# XIAO-MIC.net
KiCad netlist of a schematic drawn in EAGLE
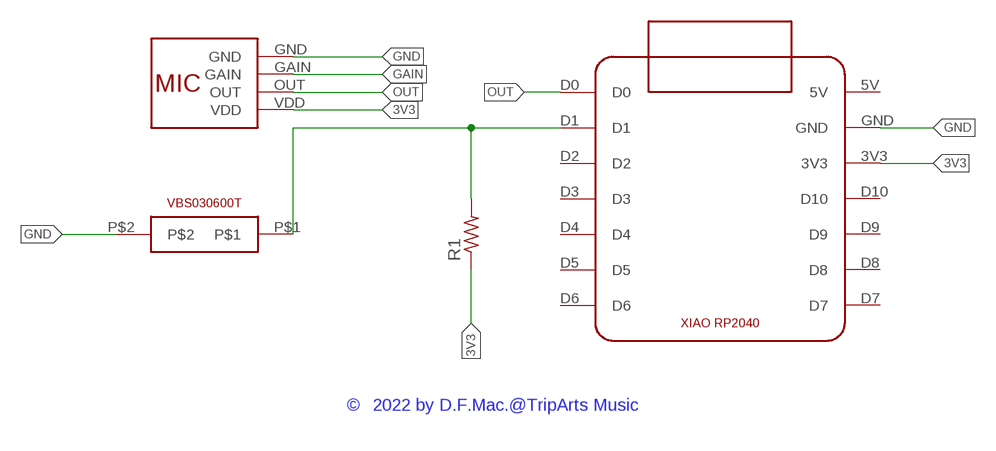
[diagram p0: schematic, sheet 1]

(export (version "E")
  (design (tool "Eeschema 10.0.6"))
  (components
    (comp (ref "R1")
      (value "R-US_R0805")
      (footprint "eagle-import:R0805")
      (libsource (lib "eagle-import") (part "R-US_R0805"))
    )
    (comp (ref "U$1")
      (value "MEMS-MIC")
      (footprint "eagle-import:MEMS-MIC-LANGLE")
      (libsource (lib "eagle-import") (part "MEMS-MIC"))
    )
    (comp (ref "U$2")
      (value "VBS030600T")
      (footprint "eagle-import:VBS030600T")
      (libsource (lib "eagle-import") (part "VBS030600T"))
    )
    (comp (ref "U$3")
      (value "XIAO-RP2040")
      (footprint "eagle-import:XIAO-RP2040")
      (libsource (lib "eagle-import") (part "XIAO-RP2040"))
    )
  )
  (nets
    (net (code "1") (name "3V3") (class "Default")
      (node (ref "R1") (pin "1") (pinfunction "1_1") (pintype "passive"))
      (node (ref "U$1") (pin "VDD") (pinfunction "VDD_VDD") (pintype "bidirectional"))
      (node (ref "U$3") (pin "3V3") (pinfunction "3V3_3V3") (pintype "bidirectional"))
    )
    (net (code "2") (name "GAIN") (class "Default")
      (node (ref "U$1") (pin "GAIN") (pinfunction "GAIN_GAIN") (pintype "bidirectional"))
    )
    (net (code "3") (name "GND") (class "Default")
      (node (ref "U$1") (pin "GND") (pinfunction "GND_GND") (pintype "bidirectional"))
      (node (ref "U$2") (pin "P$2") (pinfunction "P$2_P$2") (pintype "bidirectional"))
      (node (ref "U$3") (pin "GND") (pinfunction "GND_GND") (pintype "bidirectional"))
    )
    (net (code "4") (name "Net-(R1-Pad2)") (class "Default")
      (node (ref "R1") (pin "2") (pinfunction "2_2") (pintype "passive"))
      (node (ref "U$2") (pin "P$1") (pinfunction "P$1_P$1") (pintype "bidirectional"))
      (node (ref "U$3") (pin "D1") (pinfunction "D1_D1") (pintype "bidirectional"))
    )
    (net (code "5") (name "OUT") (class "Default")
      (node (ref "U$1") (pin "OUT") (pinfunction "OUT_OUT") (pintype "bidirectional"))
      (node (ref "U$3") (pin "D0") (pinfunction "D0_D0") (pintype "bidirectional"))
    )
    (net (code "6") (name "unconnected-(U$3-Pad5V)") (class "Default")
      (node (ref "U$3") (pin "5V") (pinfunction "5V_5V") (pintype "bidirectional"))
    )
    (net (code "7") (name "unconnected-(U$3-PadD2)") (class "Default")
      (node (ref "U$3") (pin "D2") (pinfunction "D2_D2") (pintype "bidirectional"))
    )
    (net (code "8") (name "unconnected-(U$3-PadD3)") (class "Default")
      (node (ref "U$3") (pin "D3") (pinfunction "D3_D3") (pintype "bidirectional"))
    )
    (net (code "9") (name "unconnected-(U$3-PadD4)") (class "Default")
      (node (ref "U$3") (pin "D4") (pinfunction "D4_D4") (pintype "bidirectional"))
    )
    (net (code "10") (name "unconnected-(U$3-PadD5)") (class "Default")
      (node (ref "U$3") (pin "D5") (pinfunction "D5_D5") (pintype "bidirectional"))
    )
    (net (code "11") (name "unconnected-(U$3-PadD6)") (class "Default")
      (node (ref "U$3") (pin "D6") (pinfunction "D6_D6") (pintype "bidirectional"))
    )
    (net (code "12") (name "unconnected-(U$3-PadD7)") (class "Default")
      (node (ref "U$3") (pin "D7") (pinfunction "D7_D7") (pintype "bidirectional"))
    )
    (net (code "13") (name "unconnected-(U$3-PadD8)") (class "Default")
      (node (ref "U$3") (pin "D8") (pinfunction "D8_D8") (pintype "bidirectional"))
    )
    (net (code "14") (name "unconnected-(U$3-PadD9)") (class "Default")
      (node (ref "U$3") (pin "D9") (pinfunction "D9_D9") (pintype "bidirectional"))
    )
    (net (code "15") (name "unconnected-(U$3-PadD10)") (class "Default")
      (node (ref "U$3") (pin "D10") (pinfunction "D10_D10") (pintype "bidirectional"))
    )
  )
)
